# shield.net
KiCad netlist of a schematic drawn in EAGLE
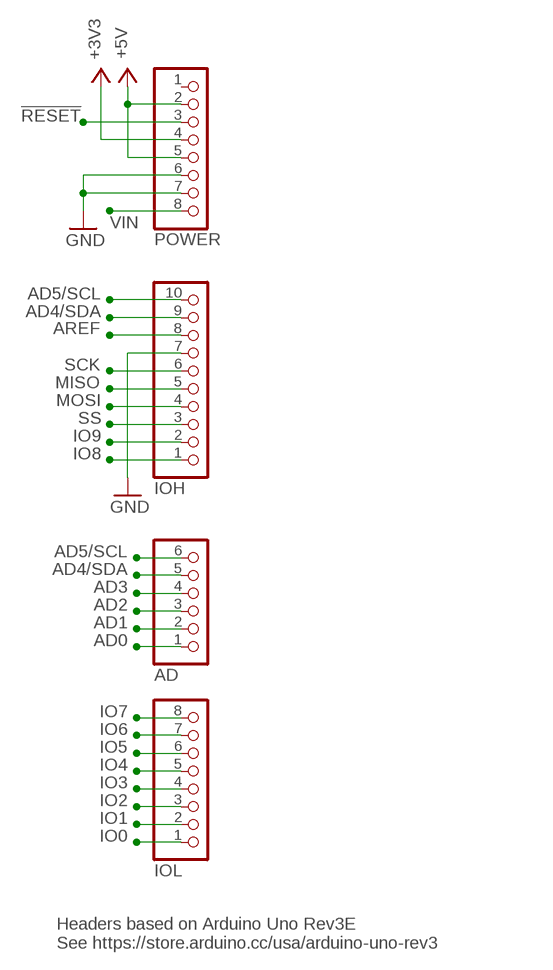
[diagram p0: schematic, sheet 1]

(export (version "E")
  (design (tool "Eeschema 10.0.6"))
  (components
    (comp (ref "AD")
      (value "6x1F-H8.5")
      (footprint "eagle-import:1X06")
      (libsource (lib "eagle-import") (part "PINHD-1X6"))
    )
    (comp (ref "IOH")
      (value "10x1F-H8.5")
      (footprint "eagle-import:1X10")
      (libsource (lib "eagle-import") (part "PINHD-1X10_ARD"))
    )
    (comp (ref "IOL")
      (value "8x1F-H8.5")
      (footprint "eagle-import:1X08")
      (libsource (lib "eagle-import") (part "PINHD-1X8"))
    )
    (comp (ref "POWER")
      (value "8x1F-H8.5")
      (footprint "eagle-import:1X08")
      (libsource (lib "eagle-import") (part "PINHD-1X8"))
    )
  )
  (nets
    (net (code "1") (name "+3V3") (class "Default")
      (node (ref "POWER") (pin "4") (pinfunction "4_4") (pintype "passive"))
    )
    (net (code "2") (name "+5V") (class "Default")
      (node (ref "POWER") (pin "2") (pinfunction "2_2") (pintype "passive"))
      (node (ref "POWER") (pin "5") (pinfunction "5_5") (pintype "passive"))
    )
    (net (code "3") (name "/AD0") (class "Default")
      (node (ref "AD") (pin "1") (pinfunction "1_1") (pintype "passive"))
    )
    (net (code "4") (name "/AD1") (class "Default")
      (node (ref "AD") (pin "2") (pinfunction "2_2") (pintype "passive"))
    )
    (net (code "5") (name "/AD2") (class "Default")
      (node (ref "AD") (pin "3") (pinfunction "3_3") (pintype "passive"))
    )
    (net (code "6") (name "/AD3") (class "Default")
      (node (ref "AD") (pin "4") (pinfunction "4_4") (pintype "passive"))
    )
    (net (code "7") (name "/AD4{slash}SDA") (class "Default")
      (node (ref "AD") (pin "5") (pinfunction "5_5") (pintype "passive"))
      (node (ref "IOH") (pin "9") (pinfunction "9_9") (pintype "passive"))
    )
    (net (code "8") (name "/AD5{slash}SCL") (class "Default")
      (node (ref "AD") (pin "6") (pinfunction "6_6") (pintype "passive"))
      (node (ref "IOH") (pin "10") (pinfunction "10_10") (pintype "passive"))
    )
    (net (code "9") (name "/AREF") (class "Default")
      (node (ref "IOH") (pin "8") (pinfunction "8_8") (pintype "passive"))
    )
    (net (code "10") (name "/IO0") (class "Default")
      (node (ref "IOL") (pin "1") (pinfunction "1_1") (pintype "passive"))
    )
    (net (code "11") (name "/IO1") (class "Default")
      (node (ref "IOL") (pin "2") (pinfunction "2_2") (pintype "passive"))
    )
    (net (code "12") (name "/IO2") (class "Default")
      (node (ref "IOL") (pin "3") (pinfunction "3_3") (pintype "passive"))
    )
    (net (code "13") (name "/IO3") (class "Default")
      (node (ref "IOL") (pin "4") (pinfunction "4_4") (pintype "passive"))
    )
    (net (code "14") (name "/IO4") (class "Default")
      (node (ref "IOL") (pin "5") (pinfunction "5_5") (pintype "passive"))
    )
    (net (code "15") (name "/IO5") (class "Default")
      (node (ref "IOL") (pin "6") (pinfunction "6_6") (pintype "passive"))
    )
    (net (code "16") (name "/IO6") (class "Default")
      (node (ref "IOL") (pin "7") (pinfunction "7_7") (pintype "passive"))
    )
    (net (code "17") (name "/IO7") (class "Default")
      (node (ref "IOL") (pin "8") (pinfunction "8_8") (pintype "passive"))
    )
    (net (code "18") (name "/IO8") (class "Default")
      (node (ref "IOH") (pin "1") (pinfunction "1_1") (pintype "passive"))
    )
    (net (code "19") (name "/IO9") (class "Default")
      (node (ref "IOH") (pin "2") (pinfunction "2_2") (pintype "passive"))
    )
    (net (code "20") (name "/MISO") (class "Default")
      (node (ref "IOH") (pin "5") (pinfunction "5_5") (pintype "passive"))
    )
    (net (code "21") (name "/MOSI") (class "Default")
      (node (ref "IOH") (pin "4") (pinfunction "4_4") (pintype "passive"))
    )
    (net (code "22") (name "/SCK") (class "Default")
      (node (ref "IOH") (pin "6") (pinfunction "6_6") (pintype "passive"))
    )
    (net (code "23") (name "/SS") (class "Default")
      (node (ref "IOH") (pin "3") (pinfunction "3_3") (pintype "passive"))
    )
    (net (code "24") (name "/VIN") (class "Default")
      (node (ref "POWER") (pin "8") (pinfunction "8_8") (pintype "passive"))
    )
    (net (code "25") (name "/~{RESET}") (class "Default")
      (node (ref "POWER") (pin "3") (pinfunction "3_3") (pintype "passive"))
    )
    (net (code "26") (name "GND") (class "Default")
      (node (ref "IOH") (pin "7") (pinfunction "7_7") (pintype "passive"))
      (node (ref "POWER") (pin "6") (pinfunction "6_6") (pintype "passive"))
      (node (ref "POWER") (pin "7") (pinfunction "7_7") (pintype "passive"))
    )
    (net (code "27") (name "unconnected-(POWER-Pad1)") (class "Default")
      (node (ref "POWER") (pin "1") (pinfunction "1_1") (pintype "passive"))
    )
  )
)
